# leonardo32u4hvpp.net
KiCad netlist of a schematic drawn in EAGLE
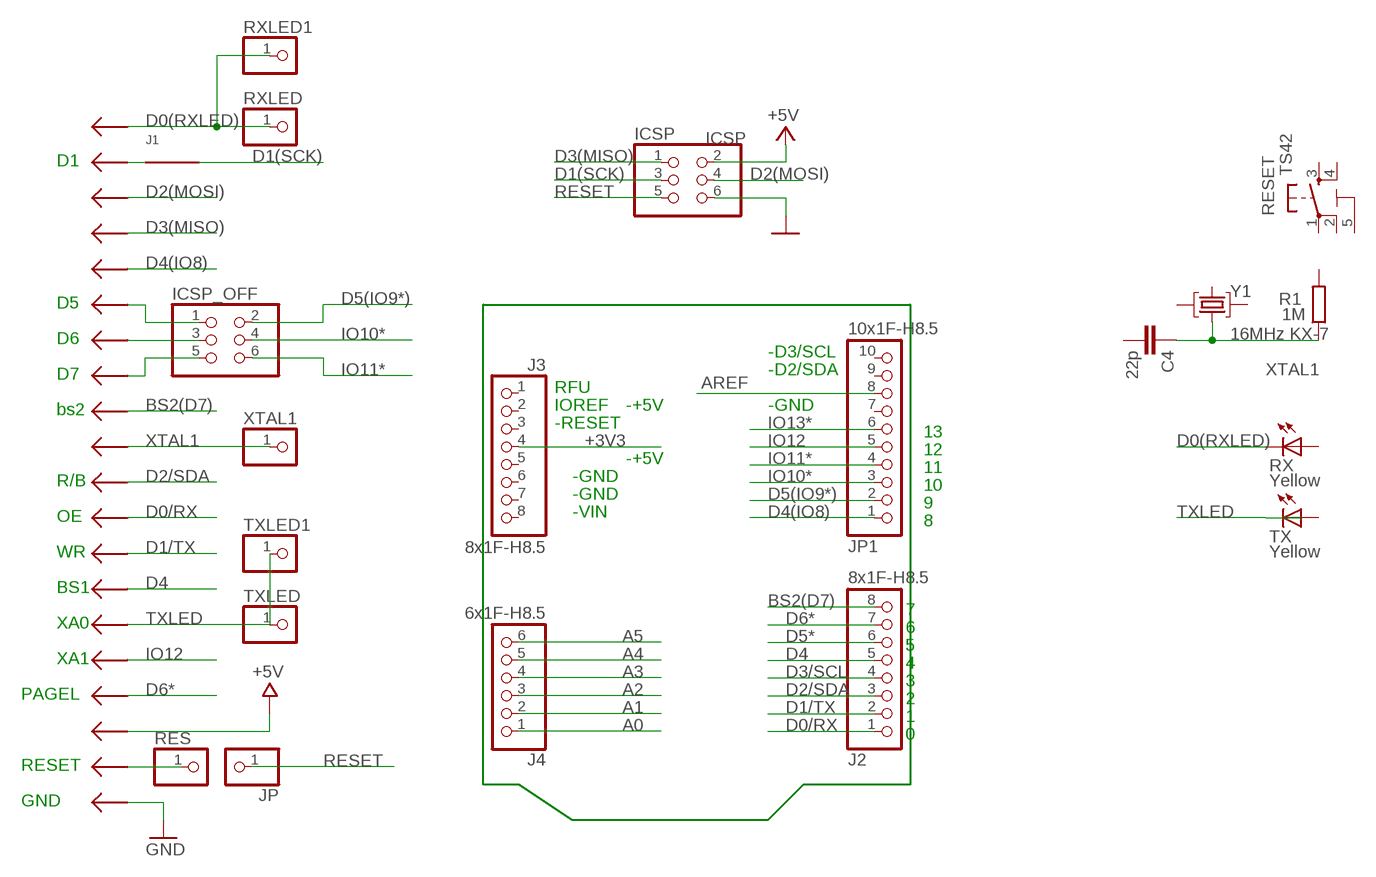
[diagram p0: schematic, sheet 1]

(export (version "E")
  (design (tool "Eeschema 10.0.6"))
  (components
    (comp (ref "C4")
      (value "22p")
      (footprint "eagle-import:C0603-ROUND")
      (libsource (lib "eagle-import") (part "C-EUC0603"))
    )
    (comp (ref "ICSP")
      (value "ICSP")
      (footprint "eagle-import:2X03")
      (libsource (lib "eagle-import") (part "PINHD-2X3"))
    )
    (comp (ref "ICSP_OFF")
      (value "PINHD-2X3")
      (footprint "eagle-import:2X03")
      (libsource (lib "eagle-import") (part "PINHD-2X3"))
    )
    (comp (ref "J1")
      (value "J")
      (footprint "eagle-import:R1206W")
      (libsource (lib "eagle-import") (part "J"))
    )
    (comp (ref "J2")
      (value "8x1F-H8.5")
      (footprint "eagle-import:1X08")
      (libsource (lib "eagle-import") (part "PINHD-1X8"))
    )
    (comp (ref "J3")
      (value "8x1F-H8.5")
      (footprint "eagle-import:1X08")
      (libsource (lib "eagle-import") (part "PINHD-1X8"))
    )
    (comp (ref "J4")
      (value "6x1F-H8.5")
      (footprint "eagle-import:1X06")
      (libsource (lib "eagle-import") (part "PINHD-1X6"))
    )
    (comp (ref "JP")
      (value "PINHD-1X1")
      (footprint "eagle-import:1X01")
      (libsource (lib "eagle-import") (part "PINHD-1X1"))
    )
    (comp (ref "JP1")
      (value "10x1F-H8.5")
      (footprint "eagle-import:1X10")
      (libsource (lib "eagle-import") (part "PINHD-1X10"))
    )
    (comp (ref "R1")
      (value "1M")
      (footprint "eagle-import:R0603-ROUND")
      (libsource (lib "eagle-import") (part "R-EU_R0603"))
    )
    (comp (ref "RES")
      (value "PINHD-1X1")
      (footprint "eagle-import:1X01")
      (libsource (lib "eagle-import") (part "PINHD-1X1"))
    )
    (comp (ref "RESET")
      (value "TS42")
      (footprint "eagle-import:TS42")
      (libsource (lib "eagle-import") (part "TS42"))
    )
    (comp (ref "RX")
      (value "Yellow")
      (footprint "eagle-import:CHIPLED_0805")
      (libsource (lib "eagle-import") (part "LEDCHIPLED_0805"))
    )
    (comp (ref "RXLED")
      (value "PINHD-1X1")
      (footprint "eagle-import:1X01")
      (libsource (lib "eagle-import") (part "PINHD-1X1"))
    )
    (comp (ref "RXLED1")
      (value "PINHD-1X1")
      (footprint "eagle-import:1X01")
      (libsource (lib "eagle-import") (part "PINHD-1X1"))
    )
    (comp (ref "TX")
      (value "Yellow")
      (footprint "eagle-import:CHIPLED_0805")
      (libsource (lib "eagle-import") (part "LEDCHIPLED_0805"))
    )
    (comp (ref "TXLED")
      (value "PINHD-1X1")
      (footprint "eagle-import:1X01")
      (libsource (lib "eagle-import") (part "PINHD-1X1"))
    )
    (comp (ref "TXLED1")
      (value "PINHD-1X1")
      (footprint "eagle-import:1X01")
      (libsource (lib "eagle-import") (part "PINHD-1X1"))
    )
    (comp (ref "U$2")
      (value "PROGRAMMER_P_AVR")
      (footprint "eagle-import:PROGRAMMER_P_AVR")
      (libsource (lib "eagle-import") (part "PROGRAMMER_P_AVR"))
    )
    (comp (ref "XTAL1")
      (value "PINHD-1X1")
      (footprint "eagle-import:1X01")
      (libsource (lib "eagle-import") (part "PINHD-1X1"))
    )
    (comp (ref "Y1")
      (value "16MHz KX-7")
      (footprint "eagle-import:CRYSTAL-3.2-2.5")
      (libsource (lib "eagle-import") (part "CRYSTAL-3.2-2.5"))
    )
  )
  (nets
    (net (code "1") (name "+5V") (class "Default")
      (node (ref "ICSP") (pin "2") (pinfunction "2_2") (pintype "passive"))
      (node (ref "U$2") (pin "VCC") (pinfunction "VCC_VCC") (pintype "bidirectional"))
    )
    (net (code "2") (name "/+3V3") (class "Default")
      (node (ref "J3") (pin "4") (pinfunction "4_4") (pintype "passive"))
    )
    (net (code "3") (name "/5-GND") (class "Default")
      (node (ref "RESET") (pin "5") (pinfunction "5-GND_5") (pintype "power_in"))
    )
    (net (code "4") (name "/A0") (class "Default")
      (node (ref "J4") (pin "1") (pinfunction "1_1") (pintype "passive"))
    )
    (net (code "5") (name "/A1") (class "Default")
      (node (ref "J4") (pin "2") (pinfunction "2_2") (pintype "passive"))
    )
    (net (code "6") (name "/A2") (class "Default")
      (node (ref "J4") (pin "3") (pinfunction "3_3") (pintype "passive"))
    )
    (net (code "7") (name "/A3") (class "Default")
      (node (ref "J4") (pin "4") (pinfunction "4_4") (pintype "passive"))
    )
    (net (code "8") (name "/A4") (class "Default")
      (node (ref "J4") (pin "5") (pinfunction "5_5") (pintype "passive"))
    )
    (net (code "9") (name "/A5") (class "Default")
      (node (ref "J4") (pin "6") (pinfunction "6_6") (pintype "passive"))
    )
    (net (code "10") (name "/AREF") (class "Default")
      (node (ref "JP1") (pin "8") (pinfunction "8_8") (pintype "passive"))
    )
    (net (code "11") (name "/BS2(D7)") (class "Default")
      (node (ref "J2") (pin "8") (pinfunction "8_8") (pintype "passive"))
      (node (ref "U$2") (pin "BS2") (pinfunction "BS2_BS2") (pintype "bidirectional"))
    )
    (net (code "12") (name "/D0(RXLED)") (class "Default")
      (node (ref "RX") (pin "C") (pinfunction "C_C") (pintype "passive"))
      (node (ref "RXLED") (pin "1") (pinfunction "1_1") (pintype "passive"))
      (node (ref "RXLED1") (pin "1") (pinfunction "1_1") (pintype "passive"))
      (node (ref "U$2") (pin "D0") (pinfunction "D0_D0") (pintype "bidirectional"))
    )
    (net (code "13") (name "/D0{slash}RX") (class "Default")
      (node (ref "J2") (pin "1") (pinfunction "1_1") (pintype "passive"))
      (node (ref "U$2") (pin "OE") (pinfunction "OE_OE") (pintype "bidirectional"))
    )
    (net (code "14") (name "/D1(SCK)") (class "Default")
      (node (ref "ICSP") (pin "3") (pinfunction "3_3") (pintype "passive"))
      (node (ref "J1") (pin "1") (pinfunction "P$1_1") (pintype "bidirectional"))
    )
    (net (code "15") (name "/D1{slash}TX") (class "Default")
      (node (ref "J2") (pin "2") (pinfunction "2_2") (pintype "passive"))
      (node (ref "U$2") (pin "WR") (pinfunction "WR_WR") (pintype "bidirectional"))
    )
    (net (code "16") (name "/D2(MOSI)") (class "Default")
      (node (ref "ICSP") (pin "4") (pinfunction "4_4") (pintype "passive"))
      (node (ref "U$2") (pin "D2") (pinfunction "D2_D2") (pintype "bidirectional"))
    )
    (net (code "17") (name "/D2{slash}SDA") (class "Default")
      (node (ref "J2") (pin "3") (pinfunction "3_3") (pintype "passive"))
      (node (ref "U$2") (pin "RB") (pinfunction "RB_RB") (pintype "bidirectional"))
    )
    (net (code "18") (name "/D3(MISO)") (class "Default")
      (node (ref "ICSP") (pin "1") (pinfunction "1_1") (pintype "passive"))
      (node (ref "U$2") (pin "D3") (pinfunction "D3_D3") (pintype "bidirectional"))
    )
    (net (code "19") (name "/D3{slash}SCL") (class "Default")
      (node (ref "J2") (pin "4") (pinfunction "4_4") (pintype "passive"))
    )
    (net (code "20") (name "/D4") (class "Default")
      (node (ref "J2") (pin "5") (pinfunction "5_5") (pintype "passive"))
      (node (ref "U$2") (pin "BS1") (pinfunction "BS1_BS1") (pintype "bidirectional"))
    )
    (net (code "21") (name "/D4(IO8)") (class "Default")
      (node (ref "JP1") (pin "1") (pinfunction "1_1") (pintype "passive"))
      (node (ref "U$2") (pin "D4") (pinfunction "D4_D4") (pintype "bidirectional"))
    )
    (net (code "22") (name "/D5(IO9*)") (class "Default")
      (node (ref "ICSP_OFF") (pin "2") (pinfunction "2_2") (pintype "passive"))
      (node (ref "JP1") (pin "2") (pinfunction "2_2") (pintype "passive"))
    )
    (net (code "23") (name "/D5*") (class "Default")
      (node (ref "J2") (pin "6") (pinfunction "6_6") (pintype "passive"))
    )
    (net (code "24") (name "/D6*") (class "Default")
      (node (ref "J2") (pin "7") (pinfunction "7_7") (pintype "passive"))
      (node (ref "U$2") (pin "PAGEL") (pinfunction "PAGEL_PAGEL") (pintype "bidirectional"))
    )
    (net (code "25") (name "/IO10*") (class "Default")
      (node (ref "ICSP_OFF") (pin "4") (pinfunction "4_4") (pintype "passive"))
      (node (ref "JP1") (pin "3") (pinfunction "3_3") (pintype "passive"))
    )
    (net (code "26") (name "/IO11*") (class "Default")
      (node (ref "ICSP_OFF") (pin "6") (pinfunction "6_6") (pintype "passive"))
      (node (ref "JP1") (pin "4") (pinfunction "4_4") (pintype "passive"))
    )
    (net (code "27") (name "/IO12") (class "Default")
      (node (ref "JP1") (pin "5") (pinfunction "5_5") (pintype "passive"))
      (node (ref "U$2") (pin "XA1") (pinfunction "XA1_XA1") (pintype "bidirectional"))
    )
    (net (code "28") (name "/IO13*") (class "Default")
      (node (ref "JP1") (pin "6") (pinfunction "6_6") (pintype "passive"))
    )
    (net (code "29") (name "/RESET") (class "Default")
      (node (ref "ICSP") (pin "5") (pinfunction "5_5") (pintype "passive"))
      (node (ref "JP") (pin "1") (pinfunction "1_1") (pintype "passive"))
    )
    (net (code "30") (name "/TXLED") (class "Default")
      (node (ref "TX") (pin "C") (pinfunction "C_C") (pintype "passive"))
      (node (ref "TXLED") (pin "1") (pinfunction "1_1") (pintype "passive"))
      (node (ref "TXLED1") (pin "1") (pinfunction "1_1") (pintype "passive"))
      (node (ref "U$2") (pin "XA0") (pinfunction "XA0_XA0") (pintype "bidirectional"))
    )
    (net (code "31") (name "/XTAL1") (class "Default")
      (node (ref "C4") (pin "1") (pinfunction "1_1") (pintype "passive"))
      (node (ref "R1") (pin "1") (pinfunction "1_1") (pintype "passive"))
      (node (ref "U$2") (pin "XTAL1") (pinfunction "XTAL1_XTAL1") (pintype "bidirectional"))
      (node (ref "XTAL1") (pin "1") (pinfunction "1_1") (pintype "passive"))
      (node (ref "Y1") (pin "1") (pinfunction "C1_1") (pintype "passive"))
    )
    (net (code "32") (name "GND") (class "Default")
      (node (ref "ICSP") (pin "6") (pinfunction "6_6") (pintype "passive"))
      (node (ref "U$2") (pin "GND") (pinfunction "GND_GND") (pintype "bidirectional"))
      (node (ref "U$2") (pin "GND01") (pinfunction "GND_GND01") (pintype "bidirectional"))
      (node (ref "U$2") (pin "GND03") (pinfunction "GND_GND03") (pintype "bidirectional"))
      (node (ref "U$2") (pin "GND04") (pinfunction "GND_GND04") (pintype "bidirectional"))
      (node (ref "U$2") (pin "GND05") (pinfunction "GND_GND05") (pintype "bidirectional"))
      (node (ref "U$2") (pin "GND06") (pinfunction "GND_GND06") (pintype "bidirectional"))
      (node (ref "U$2") (pin "GND07") (pinfunction "GND_GND07") (pintype "bidirectional"))
      (node (ref "U$2") (pin "GND08") (pinfunction "GND_GND08") (pintype "bidirectional"))
      (node (ref "U$2") (pin "GND09") (pinfunction "GND_GND09") (pintype "bidirectional"))
      (node (ref "U$2") (pin "GND10") (pinfunction "GND_GND10") (pintype "bidirectional"))
      (node (ref "U$2") (pin "GND11") (pinfunction "GND_GND11") (pintype "bidirectional"))
      (node (ref "U$2") (pin "GND12") (pinfunction "GND_GND12") (pintype "bidirectional"))
      (node (ref "U$2") (pin "GND13") (pinfunction "GND_GND13") (pintype "bidirectional"))
      (node (ref "U$2") (pin "GND14") (pinfunction "GND_GND14") (pintype "bidirectional"))
      (node (ref "U$2") (pin "GND15") (pinfunction "GND_GND15") (pintype "bidirectional"))
      (node (ref "U$2") (pin "GND16") (pinfunction "GND_GND16") (pintype "bidirectional"))
      (node (ref "U$2") (pin "GND17") (pinfunction "GND_GND17") (pintype "bidirectional"))
      (node (ref "U$2") (pin "GND18") (pinfunction "GND_GND18") (pintype "bidirectional"))
      (node (ref "U$2") (pin "GND19") (pinfunction "GND_GND19") (pintype "bidirectional"))
      (node (ref "U$2") (pin "GND2") (pinfunction "GND_GND2") (pintype "bidirectional"))
      (node (ref "U$2") (pin "GND20") (pinfunction "GND_GND20") (pintype "bidirectional"))
      (node (ref "U$2") (pin "GND21") (pinfunction "GND_GND21") (pintype "bidirectional"))
      (node (ref "U$2") (pin "GND22") (pinfunction "GND_GND22") (pintype "bidirectional"))
    )
    (net (code "33") (name "Net-(ICSP_OFF-Pad1)") (class "Default")
      (node (ref "ICSP_OFF") (pin "1") (pinfunction "1_1") (pintype "passive"))
      (node (ref "U$2") (pin "D5") (pinfunction "D5_D5") (pintype "bidirectional"))
    )
    (net (code "34") (name "Net-(ICSP_OFF-Pad3)") (class "Default")
      (node (ref "ICSP_OFF") (pin "3") (pinfunction "3_3") (pintype "passive"))
      (node (ref "U$2") (pin "D6") (pinfunction "D6_D6") (pintype "bidirectional"))
    )
    (net (code "35") (name "Net-(ICSP_OFF-Pad5)") (class "Default")
      (node (ref "ICSP_OFF") (pin "5") (pinfunction "5_5") (pintype "passive"))
      (node (ref "U$2") (pin "D7") (pinfunction "D7_D7") (pintype "bidirectional"))
    )
    (net (code "36") (name "Net-(J1-P$2)") (class "Default")
      (node (ref "J1") (pin "2") (pinfunction "P$2_2") (pintype "bidirectional"))
      (node (ref "U$2") (pin "D1") (pinfunction "D1_D1") (pintype "bidirectional"))
    )
    (net (code "37") (name "Net-(RES-Pad1)") (class "Default")
      (node (ref "RES") (pin "1") (pinfunction "1_1") (pintype "passive"))
      (node (ref "U$2") (pin "RESET") (pinfunction "RESET_RESET") (pintype "bidirectional"))
    )
    (net (code "38") (name "unconnected-(C4-Pad2)") (class "Default")
      (node (ref "C4") (pin "2") (pinfunction "2_2") (pintype "passive"))
    )
    (net (code "39") (name "unconnected-(J3-Pad1)") (class "Default")
      (node (ref "J3") (pin "1") (pinfunction "1_1") (pintype "passive"))
    )
    (net (code "40") (name "unconnected-(J3-Pad2)") (class "Default")
      (node (ref "J3") (pin "2") (pinfunction "2_2") (pintype "passive"))
    )
    (net (code "41") (name "unconnected-(J3-Pad3)") (class "Default")
      (node (ref "J3") (pin "3") (pinfunction "3_3") (pintype "passive"))
    )
    (net (code "42") (name "unconnected-(J3-Pad5)") (class "Default")
      (node (ref "J3") (pin "5") (pinfunction "5_5") (pintype "passive"))
    )
    (net (code "43") (name "unconnected-(J3-Pad6)") (class "Default")
      (node (ref "J3") (pin "6") (pinfunction "6_6") (pintype "passive"))
    )
    (net (code "44") (name "unconnected-(J3-Pad7)") (class "Default")
      (node (ref "J3") (pin "7") (pinfunction "7_7") (pintype "passive"))
    )
    (net (code "45") (name "unconnected-(J3-Pad8)") (class "Default")
      (node (ref "J3") (pin "8") (pinfunction "8_8") (pintype "passive"))
    )
    (net (code "46") (name "unconnected-(JP1-Pad7)") (class "Default")
      (node (ref "JP1") (pin "7") (pinfunction "7_7") (pintype "passive"))
    )
    (net (code "47") (name "unconnected-(JP1-Pad9)") (class "Default")
      (node (ref "JP1") (pin "9") (pinfunction "9_9") (pintype "passive"))
    )
    (net (code "48") (name "unconnected-(JP1-Pad10)") (class "Default")
      (node (ref "JP1") (pin "10") (pinfunction "10_10") (pintype "passive"))
    )
    (net (code "49") (name "unconnected-(R1-Pad2)") (class "Default")
      (node (ref "R1") (pin "2") (pinfunction "2_2") (pintype "passive"))
    )
    (net (code "50") (name "unconnected-(RESET-Pad1)") (class "Default")
      (node (ref "RESET") (pin "1") (pinfunction "1_1") (pintype "passive"))
    )
    (net (code "51") (name "unconnected-(RESET-Pad2)") (class "Default")
      (node (ref "RESET") (pin "2") (pinfunction "2_2") (pintype "passive"))
    )
    (net (code "52") (name "unconnected-(RESET-Pad3)") (class "Default")
      (node (ref "RESET") (pin "3") (pinfunction "3_3") (pintype "passive"))
    )
    (net (code "53") (name "unconnected-(RESET-Pad4)") (class "Default")
      (node (ref "RESET") (pin "4") (pinfunction "4_4") (pintype "passive"))
    )
    (net (code "54") (name "unconnected-(RX-PadA)") (class "Default")
      (node (ref "RX") (pin "A") (pinfunction "A_A") (pintype "passive"))
    )
    (net (code "55") (name "unconnected-(TX-PadA)") (class "Default")
      (node (ref "TX") (pin "A") (pinfunction "A_A") (pintype "passive"))
    )
    (net (code "56") (name "unconnected-(Y1-C2-Pad3)") (class "Default")
      (node (ref "Y1") (pin "3") (pinfunction "C2_3") (pintype "passive"))
    )
    (net (code "57") (name "unconnected-(Y1-GND-Pad2)") (class "Default")
      (node (ref "Y1") (pin "2") (pinfunction "GND_2") (pintype "passive"))
    )
    (net (code "58") (name "unconnected-(Y1-GND-Pad4)") (class "Default")
      (node (ref "Y1") (pin "4") (pinfunction "GND_4") (pintype "passive"))
    )
  )
)
